# 200_Peripherals_Sensors.net
KiCad netlist of a schematic drawn in Altium Designer
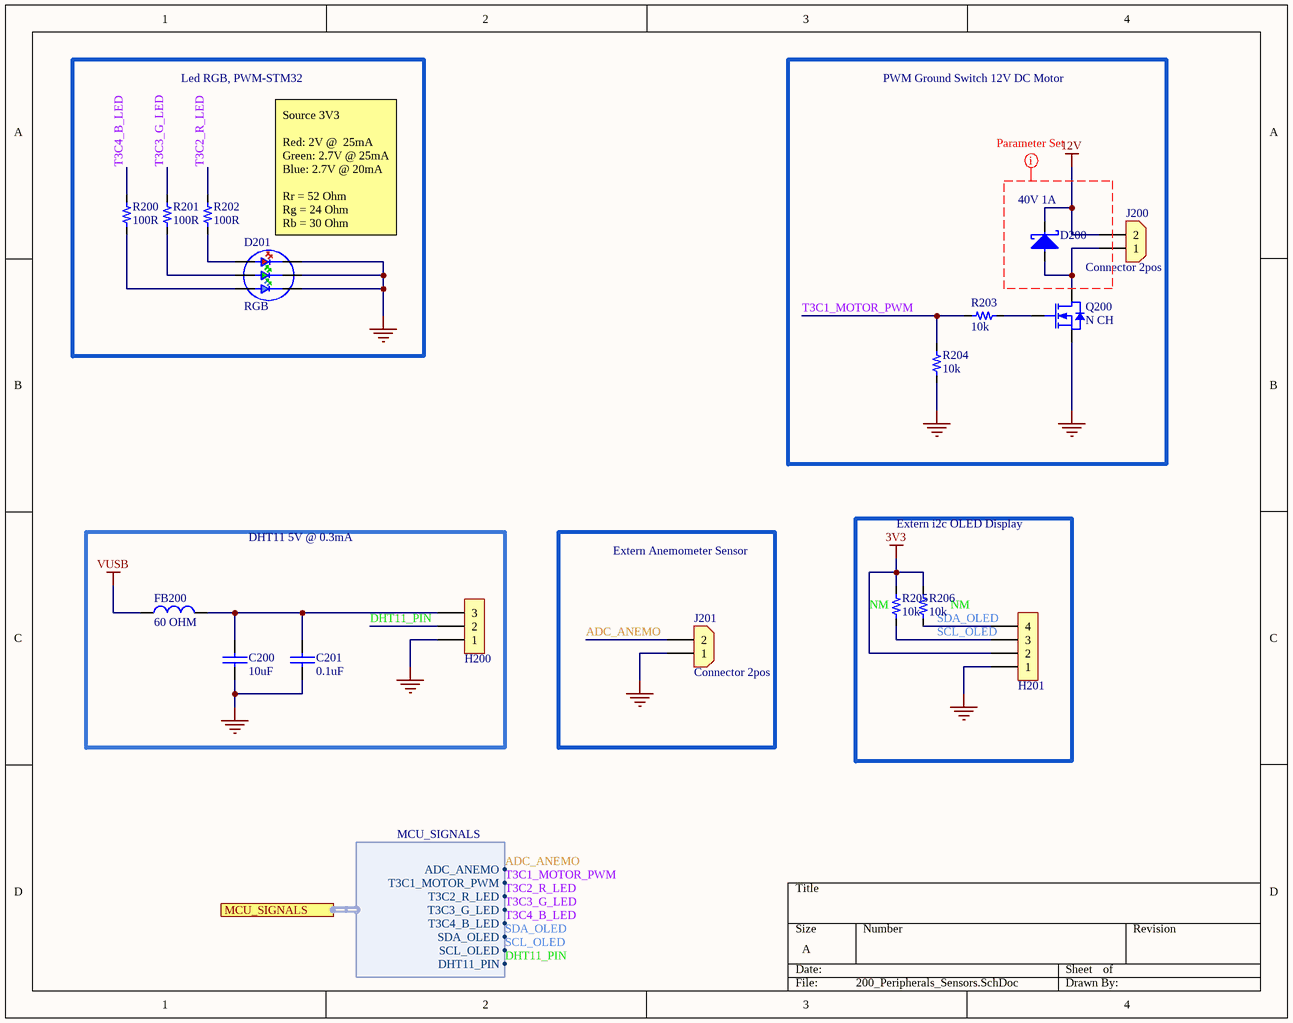
[diagram p0: 200_Peripherals_Sensors.SchDoc]

(export (version "E")
  (design (tool "Eeschema 10.0.6"))
  (components
    (comp (ref "C200")
      (value "10uF")
      (footprint "0805_cap")
      (description "25V 10uF X5R ±10% 0805 Multilayer Ceramic Capacitors MLCC - SMD/SMT ROHS")
      (fields
        (field (name "MANUFACTURER") "Samsung Electro-Mechanics")
        (field (name "MANUFACTURER PART NUMBER") "CL21A106KAYNNNE")
      )
      (libsource (lib "shared_lib") (part "Cap_10uF_0805_25V_"))
    )
    (comp (ref "C201")
      (value "0.1uF")
      (footprint "0603_cap")
      (description "50V 100nF Y5V -20%~+80% 0603 Multilayer Ceramic Capacitors MLCC - SMD/SMT ROHS")
      (fields
        (field (name "MANUFACTURER") "Walsin Tech Corp")
        (field (name "MANUFACTURER PART NUMBER") "0603F104Z500CT")
      )
      (libsource (lib "shared_lib") (part "Cap_0.1uF_0603_50V"))
    )
    (comp (ref "D200")
      (value "40V 1A")
      (footprint "SOD_123")
      (description "DIODE SCHOTTKY 40V 1A SOD123F")
      (fields
        (field (name "MANUFACTURER") "Shanghai Prisemi Elec")
        (field (name "MANUFACTURER PART NUMBER") "PSBD1DF40V1H")
      )
      (libsource (lib "shared_lib") (part "D_Schottky_40V_1A_SOD_123F"))
    )
    (comp (ref "D201")
      (value "RGB")
      (footprint "RGB_NS_3.5X3.7")
      (description "-30℃~+85℃ RGB 110° 3535(mm) Light Emitting Diodes (LED) ROHS")
      (fields
        (field (name "MANUFACTURER") "Foshan NationStar Optoelectronics")
        (field (name "MANUFACTURER PART NUMBER") "RS-3535MWAM")
      )
      (libsource (lib "shared_lib") (part "LED_RGB_3535_SMD"))
    )
    (comp (ref "FB200")
      (value "60 OHM")
      (footprint "0603_fb")
      (description "2A 1 100mΩ 60Ω@100MHz ±25% 0603 Ferrite Beads ROHS")
      (fields
        (field (name "MANUFACTURER") "TAI-TECH")
        (field (name "MANUFACTURER PART NUMBER") "HCB1608KF-600T20")
      )
      (libsource (lib "shared_lib") (part "FB_60_0603_2A"))
    )
    (comp (ref "H200")
      (value "3x1")
      (footprint "H_3X1_TH_100mil")
      (description "H_Male_3x1_TH_100mil")
      (libsource (lib "shared_lib") (part "H_Male_3x1_TH_100mil"))
    )
    (comp (ref "H201")
      (value "4x1")
      (footprint "H_4x1_TH_2.54mm")
      (description "H_Male_4x1_TH_100mil")
      (libsource (lib "shared_lib") (part "H_Male_4x1_TH_100mil"))
    )
    (comp (ref "J200")
      (value "Connector 2pos")
      (footprint "CON_2x1_TH_5MM")
      (description "2POS 5MM")
      (fields (field (name "MANUFACTURER") "JILN") (field (name "MANUFACTURER PART NUMBER") "JL126-50002G01"))
      (libsource (lib "shared_lib") (part "Con_2x1_TH_5mm"))
    )
    (comp (ref "J201")
      (value "Connector 2pos")
      (footprint "CON_2x1_TH_5MM")
      (description "2POS 5MM")
      (fields (field (name "MANUFACTURER") "JILN") (field (name "MANUFACTURER PART NUMBER") "JL126-50002G01"))
      (libsource (lib "shared_lib") (part "Con_2x1_TH_5mm"))
    )
    (comp (ref "Q200")
      (value "N CH")
      (footprint "SOT_23_3")
      (description "MOSFET N-CH 20V SOT23")
      (fields (field (name "MANUFACTURER") "Doeshare") (field (name "MANUFACTURER PART NUMBER") "DN2302S"))
      (libsource (lib "shared_lib") (part "Q_NFET_20V_3.2A_SOT23"))
    )
    (comp (ref "R200")
      (value "100R")
      (footprint "0603_res")
      (description "RES SMD 100R OHM 5% 1/10W 0603")
      (fields
        (field (name "MANUFACTURER") "FOJAN")
        (field (name "MANUFACTURER PART NUMBER") "FRC0603J101 TS")
      )
      (libsource (lib "shared_lib") (part "Res_100R_0603_1/10W"))
    )
    (comp (ref "R201")
      (value "100R")
      (footprint "0603_res")
      (description "RES SMD 100R OHM 5% 1/10W 0603")
      (fields
        (field (name "MANUFACTURER") "FOJAN")
        (field (name "MANUFACTURER PART NUMBER") "FRC0603J101 TS")
      )
      (libsource (lib "shared_lib") (part "Res_100R_0603_1/10W"))
    )
    (comp (ref "R202")
      (value "100R")
      (footprint "0603_res")
      (description "RES SMD 100R OHM 5% 1/10W 0603")
      (fields
        (field (name "MANUFACTURER") "FOJAN")
        (field (name "MANUFACTURER PART NUMBER") "FRC0603J101 TS")
      )
      (libsource (lib "shared_lib") (part "Res_100R_0603_1/10W"))
    )
    (comp (ref "R203")
      (value "10k")
      (footprint "0603_res")
      (description "RES SMD 10k OHM 5% 1/10W 0603")
      (fields (field (name "MANUFACTURER") "FOJAN") (field (name "MANUFACTURER PART NUMBER") "FRC0603J103TS"))
      (libsource (lib "shared_lib") (part "Res_10k_0603_1/10W"))
    )
    (comp (ref "R204")
      (value "10k")
      (footprint "0603_res")
      (description "RES SMD 10k OHM 5% 1/10W 0603")
      (fields (field (name "MANUFACTURER") "FOJAN") (field (name "MANUFACTURER PART NUMBER") "FRC0603J103TS"))
      (libsource (lib "shared_lib") (part "Res_10k_0603_1/10W"))
    )
    (comp (ref "R205")
      (value "10k")
      (footprint "0603_res")
      (description "RES SMD 10k OHM 5% 1/10W 0603")
      (fields
        (field (name "USAGE") "NM")
        (field (name "MANUFACTURER") "FOJAN")
        (field (name "MANUFACTURER PART NUMBER") "FRC0603J103TS")
      )
      (libsource (lib "shared_lib") (part "Res_10k_0603_1/10W"))
    )
    (comp (ref "R206")
      (value "10k")
      (footprint "0603_res")
      (description "RES SMD 10k OHM 5% 1/10W 0603")
      (fields
        (field (name "USAGE") "NM")
        (field (name "MANUFACTURER") "FOJAN")
        (field (name "MANUFACTURER PART NUMBER") "FRC0603J103TS")
      )
      (libsource (lib "shared_lib") (part "Res_10k_0603_1/10W"))
    )
  )
  (nets
    (net (code "2") (name "/ADC_ANEMO") (class "Default")
      (node (ref "J201") (pin "2") (pinfunction "2_2") (pintype "passive"))
    )
    (net (code "3") (name "/DHT11_PIN") (class "Default")
      (node (ref "H200") (pin "2") (pinfunction "2_2") (pintype "passive"))
    )
    (net (code "4") (name "/SCL_OLED") (class "Default")
      (node (ref "H201") (pin "3") (pinfunction "3_3") (pintype "passive"))
      (node (ref "R205") (pin "1") (pinfunction "1_1") (pintype "passive"))
    )
    (net (code "5") (name "/SDA_OLED") (class "Default")
      (node (ref "H201") (pin "4") (pinfunction "4_4") (pintype "passive"))
      (node (ref "R206") (pin "1") (pinfunction "1_1") (pintype "passive"))
    )
    (net (code "6") (name "/T3C1_MOTOR_PWM") (class "Default")
      (node (ref "R203") (pin "2") (pinfunction "2_2") (pintype "passive"))
      (node (ref "R204") (pin "2") (pinfunction "2_2") (pintype "passive"))
    )
    (net (code "7") (name "/T3C2_R_LED") (class "Default")
      (node (ref "R202") (pin "2") (pinfunction "2_2") (pintype "passive"))
    )
    (net (code "8") (name "/T3C3_G_LED") (class "Default")
      (node (ref "R201") (pin "2") (pinfunction "2_2") (pintype "passive"))
    )
    (net (code "9") (name "/T3C4_B_LED") (class "Default")
      (node (ref "R200") (pin "2") (pinfunction "2_2") (pintype "passive"))
    )
    (net (code "11") (name "3V3") (class "Default")
      (node (ref "H201") (pin "2") (pinfunction "2_2") (pintype "passive"))
      (node (ref "R205") (pin "2") (pinfunction "2_2") (pintype "passive"))
      (node (ref "R206") (pin "2") (pinfunction "2_2") (pintype "passive"))
    )
    (net (code "12") (name "12V") (class "Default")
      (node (ref "D200") (pin "1") (pinfunction "1_1") (pintype "passive"))
      (node (ref "J200") (pin "2") (pinfunction "2_2") (pintype "passive"))
    )
    (net (code "13") (name "GND") (class "Default")
      (node (ref "C200") (pin "2") (pinfunction "2_2") (pintype "passive"))
      (node (ref "C201") (pin "2") (pinfunction "2_2") (pintype "passive"))
      (node (ref "D201") (pin "1") (pinfunction "1_1") (pintype "passive"))
      (node (ref "D201") (pin "2") (pinfunction "2_2") (pintype "passive"))
      (node (ref "D201") (pin "3") (pinfunction "3_3") (pintype "passive"))
      (node (ref "H200") (pin "1") (pinfunction "1_1") (pintype "passive"))
      (node (ref "H201") (pin "1") (pinfunction "1_1") (pintype "passive"))
      (node (ref "J201") (pin "1") (pinfunction "1_1") (pintype "passive"))
      (node (ref "Q200") (pin "2") (pinfunction "S_2") (pintype "passive"))
      (node (ref "R204") (pin "1") (pinfunction "1_1") (pintype "passive"))
    )
    (net (code "14") (name "Net-(C200-Pad1)") (class "Default")
      (node (ref "C200") (pin "1") (pinfunction "1_1") (pintype "passive"))
      (node (ref "C201") (pin "1") (pinfunction "1_1") (pintype "passive"))
      (node (ref "FB200") (pin "2") (pinfunction "2_2") (pintype "passive"))
      (node (ref "H200") (pin "3") (pinfunction "3_3") (pintype "passive"))
    )
    (net (code "15") (name "Net-(D201-Pad4)") (class "Default")
      (node (ref "D201") (pin "4") (pinfunction "4_4") (pintype "passive"))
      (node (ref "R202") (pin "1") (pinfunction "1_1") (pintype "passive"))
    )
    (net (code "16") (name "Net-(D201-Pad5)") (class "Default")
      (node (ref "D201") (pin "5") (pinfunction "5_5") (pintype "passive"))
      (node (ref "R201") (pin "1") (pinfunction "1_1") (pintype "passive"))
    )
    (net (code "17") (name "Net-(D201-Pad6)") (class "Default")
      (node (ref "D201") (pin "6") (pinfunction "6_6") (pintype "passive"))
      (node (ref "R200") (pin "1") (pinfunction "1_1") (pintype "passive"))
    )
    (net (code "18") (name "Net-(Q200-D)") (class "Default")
      (node (ref "D200") (pin "2") (pinfunction "2_2") (pintype "passive"))
      (node (ref "J200") (pin "1") (pinfunction "1_1") (pintype "passive"))
      (node (ref "Q200") (pin "3") (pinfunction "D_3") (pintype "passive"))
    )
    (net (code "19") (name "Net-(Q200-G)") (class "Default")
      (node (ref "Q200") (pin "1") (pinfunction "G_1") (pintype "passive"))
      (node (ref "R203") (pin "1") (pinfunction "1_1") (pintype "passive"))
    )
    (net (code "20") (name "VUSB") (class "Default")
      (node (ref "FB200") (pin "1") (pinfunction "1_1") (pintype "passive"))
    )
  )
)
